# Wisol-Breakout.net
KiCad netlist of a schematic drawn in EAGLE
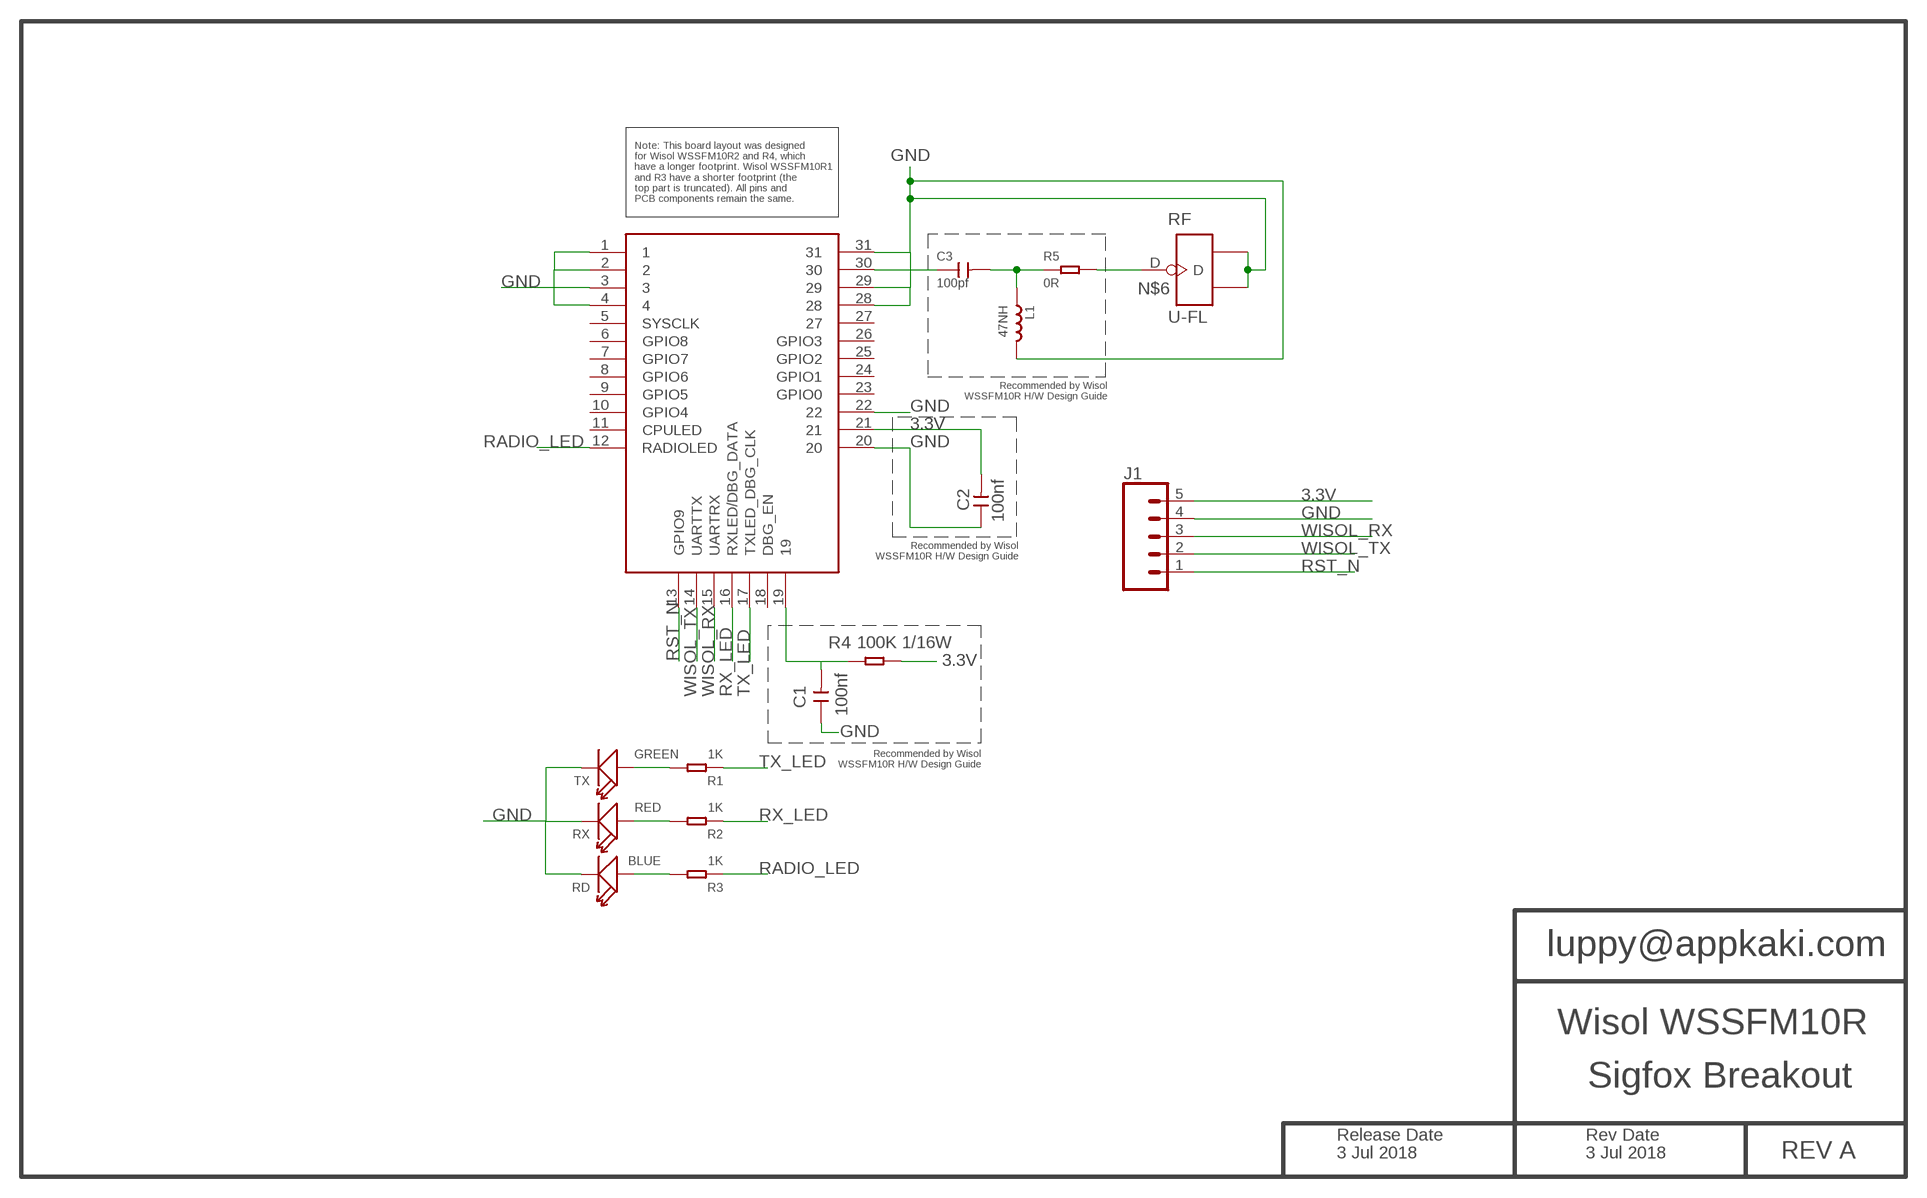
[diagram p0: schematic, sheet 1]

(export (version "E")
  (design (tool "Eeschema 10.0.6"))
  (components
    (comp (ref "C1")
      (value "100nf")
      (footprint "eagle-import:C0402")
      (fields (field (name "MPN") "CC0402KRX7R8BB104"))
      (libsource (lib "eagle-import") (part "CERAMIC-100NF-25V-10%-X7R(0402)"))
    )
    (comp (ref "C2")
      (value "100nf")
      (footprint "eagle-import:C0402")
      (fields (field (name "MPN") "CC0402KRX7R8BB104"))
      (libsource (lib "eagle-import") (part "CERAMIC-100NF-25V-10%-X7R(0402)"))
    )
    (comp (ref "C3")
      (value "100pf")
      (footprint "eagle-import:C0402")
      (fields (field (name "MPN") "CC0402JRNPO9BN101"))
      (libsource (lib "eagle-import") (part "CERAMIC-100PF-50V-5%-NPO(0402)"))
    )
    (comp (ref "J1")
      (value "CONN_05")
      (footprint "eagle-import:1X05")
      (libsource (lib "eagle-import") (part "CONN_05"))
    )
    (comp (ref "L1")
      (value "47NH")
      (footprint "eagle-import:L0402")
      (fields (field (name "MPN") "LQG15HS15NJ02") (field (name "MPN_1") "LQW15AN47NJ00D"))
      (libsource (lib "eagle-import") (part "SMD-INDUCTOR-15NH-5%-300MA(0402)"))
    )
    (comp (ref "R1")
      (value "1K")
      (footprint "eagle-import:R0402")
      (fields (field (name "MPN") "RC0402JR-071KL") (field (name "MPN_1") "RC0402FR-071KL"))
      (libsource (lib "eagle-import") (part "SMD-RES-1K-5%-1/16W(0402)"))
    )
    (comp (ref "R2")
      (value "1K")
      (footprint "eagle-import:R0402")
      (fields (field (name "MPN") "RC0402JR-071KL") (field (name "MPN_1") "RC0402FR-071KL"))
      (libsource (lib "eagle-import") (part "SMD-RES-1K-5%-1/16W(0402)"))
    )
    (comp (ref "R3")
      (value "1K")
      (footprint "eagle-import:R0402")
      (fields (field (name "MPN") "RC0402JR-071KL") (field (name "MPN_1") "RC0402FR-071KL"))
      (libsource (lib "eagle-import") (part "SMD-RES-1K-5%-1/16W(0402)"))
    )
    (comp (ref "R4")
      (value "100K 1/16W")
      (footprint "eagle-import:R0402")
      (fields (field (name "MPN") "RC0402JR-07100KL"))
      (libsource (lib "eagle-import") (part "SMD-RES-100K-5%-1/16W(0402)"))
    )
    (comp (ref "R5")
      (value "0R")
      (footprint "eagle-import:R0402")
      (fields (field (name "MPN") "RC0402JR-070RL"))
      (libsource (lib "eagle-import") (part "SMD-RES-0R-5%-1/16W(0402)"))
    )
    (comp (ref "RD")
      (value "BLUE")
      (footprint "eagle-import:LED-0603")
      (fields (field (name "MPN") "19-217-BHC-ZL1M2RY-3T"))
      (libsource (lib "eagle-import") (part "SMD-LED-CLEAR-BLUE(0603)"))
    )
    (comp (ref "RF")
      (value "U-FL")
      (footprint "eagle-import:U-FL3P-SMD-2.6X2.6X1.0MM")
      (libsource (lib "eagle-import") (part "ANTENNA-CONN-U-FL(3P)"))
    )
    (comp (ref "RX")
      (value "RED")
      (footprint "eagle-import:LED-0603")
      (fields (field (name "MPN") "19-217-R6C-AL1M2VY-3T"))
      (libsource (lib "eagle-import") (part "LED-SMD-RED-DIFFUSED(0603)"))
    )
    (comp (ref "TX")
      (value "GREEN")
      (footprint "eagle-import:LED-0603")
      (fields (field (name "MPN") "19-217-G7C-AN1P2-3T"))
      (libsource (lib "eagle-import") (part "SMD-LED-CLEAR-GREEN(0603)"))
    )
    (comp (ref "WSSFM10R")
      (value "WSSFM10RWSSFM10R2R4")
      (footprint "eagle-import:WSSFM10R")
      (libsource (lib "eagle-import") (part "WSSFM10RWSSFM10R2R4"))
    )
  )
  (nets
    (net (code "1") (name "/3.3V") (class "Default")
      (node (ref "C2") (pin "2") (pinfunction "2_2") (pintype "passive"))
      (node (ref "J1") (pin "5") (pinfunction "5_5") (pintype "passive"))
      (node (ref "R4") (pin "2") (pinfunction "2_2") (pintype "passive"))
      (node (ref "WSSFM10R") (pin "21") (pinfunction "21_21") (pintype "bidirectional"))
    )
    (net (code "2") (name "/GND") (class "Default")
      (node (ref "C1") (pin "1") (pinfunction "1_1") (pintype "passive"))
      (node (ref "C2") (pin "1") (pinfunction "1_1") (pintype "passive"))
      (node (ref "J1") (pin "4") (pinfunction "4_4") (pintype "passive"))
      (node (ref "L1") (pin "2") (pinfunction "2_2") (pintype "passive"))
      (node (ref "RD") (pin "-") (pinfunction "-_-") (pintype "passive"))
      (node (ref "RF") (pin "GND1") (pinfunction "GND1_GND1") (pintype "bidirectional"))
      (node (ref "RF") (pin "GND2") (pinfunction "GND2_GND2") (pintype "bidirectional"))
      (node (ref "RX") (pin "-") (pinfunction "-_-") (pintype "passive"))
      (node (ref "TX") (pin "-") (pinfunction "-_-") (pintype "passive"))
      (node (ref "WSSFM10R") (pin "1") (pinfunction "1_1") (pintype "bidirectional"))
      (node (ref "WSSFM10R") (pin "2") (pinfunction "2_2") (pintype "bidirectional"))
      (node (ref "WSSFM10R") (pin "20") (pinfunction "20_20") (pintype "bidirectional"))
      (node (ref "WSSFM10R") (pin "22") (pinfunction "22_22") (pintype "bidirectional"))
      (node (ref "WSSFM10R") (pin "28") (pinfunction "28_28") (pintype "bidirectional"))
      (node (ref "WSSFM10R") (pin "29") (pinfunction "29_29") (pintype "bidirectional"))
      (node (ref "WSSFM10R") (pin "3") (pinfunction "3_3") (pintype "bidirectional"))
      (node (ref "WSSFM10R") (pin "31") (pinfunction "31_31") (pintype "bidirectional"))
      (node (ref "WSSFM10R") (pin "4") (pinfunction "4_4") (pintype "bidirectional"))
    )
    (net (code "3") (name "/N$6") (class "Default")
      (node (ref "R5") (pin "2") (pinfunction "2_2") (pintype "passive"))
      (node (ref "RF") (pin "D") (pinfunction "D_D") (pintype "bidirectional"))
    )
    (net (code "4") (name "/RADIO_LED") (class "Default")
      (node (ref "R3") (pin "1") (pinfunction "1_1") (pintype "passive"))
      (node (ref "WSSFM10R") (pin "12") (pinfunction "RADIOLED_12") (pintype "bidirectional"))
    )
    (net (code "5") (name "/RST_N") (class "Default")
      (node (ref "J1") (pin "1") (pinfunction "1_1") (pintype "passive"))
      (node (ref "WSSFM10R") (pin "13") (pinfunction "GPIO9_13") (pintype "bidirectional"))
    )
    (net (code "6") (name "/RX_LED") (class "Default")
      (node (ref "R2") (pin "1") (pinfunction "1_1") (pintype "passive"))
      (node (ref "WSSFM10R") (pin "16") (pinfunction "RXLED/DBG_DATA_16") (pintype "bidirectional"))
    )
    (net (code "7") (name "/TX_LED") (class "Default")
      (node (ref "R1") (pin "1") (pinfunction "1_1") (pintype "passive"))
      (node (ref "WSSFM10R") (pin "17") (pinfunction "TXLED_DBG_CLK_17") (pintype "bidirectional"))
    )
    (net (code "8") (name "/WISOL_RX") (class "Default")
      (node (ref "J1") (pin "3") (pinfunction "3_3") (pintype "passive"))
      (node (ref "WSSFM10R") (pin "15") (pinfunction "UARTRX_15") (pintype "bidirectional"))
    )
    (net (code "9") (name "/WISOL_TX") (class "Default")
      (node (ref "J1") (pin "2") (pinfunction "2_2") (pintype "passive"))
      (node (ref "WSSFM10R") (pin "14") (pinfunction "UARTTX_14") (pintype "bidirectional"))
    )
    (net (code "10") (name "Net-(C1-Pad2)") (class "Default")
      (node (ref "C1") (pin "2") (pinfunction "2_2") (pintype "passive"))
      (node (ref "R4") (pin "1") (pinfunction "1_1") (pintype "passive"))
      (node (ref "WSSFM10R") (pin "19") (pinfunction "19_19") (pintype "bidirectional"))
    )
    (net (code "11") (name "Net-(C3-Pad1)") (class "Default")
      (node (ref "C3") (pin "1") (pinfunction "1_1") (pintype "passive"))
      (node (ref "WSSFM10R") (pin "30") (pinfunction "30_30") (pintype "bidirectional"))
    )
    (net (code "12") (name "Net-(C3-Pad2)") (class "Default")
      (node (ref "C3") (pin "2") (pinfunction "2_2") (pintype "passive"))
      (node (ref "L1") (pin "1") (pinfunction "1_1") (pintype "passive"))
      (node (ref "R5") (pin "1") (pinfunction "1_1") (pintype "passive"))
    )
    (net (code "13") (name "Net-(R1-Pad2)") (class "Default")
      (node (ref "R1") (pin "2") (pinfunction "2_2") (pintype "passive"))
      (node (ref "TX") (pin "+") (pinfunction "+_+") (pintype "passive"))
    )
    (net (code "14") (name "Net-(R2-Pad2)") (class "Default")
      (node (ref "R2") (pin "2") (pinfunction "2_2") (pintype "passive"))
      (node (ref "RX") (pin "+") (pinfunction "+_+") (pintype "passive"))
    )
    (net (code "15") (name "Net-(R3-Pad2)") (class "Default")
      (node (ref "R3") (pin "2") (pinfunction "2_2") (pintype "passive"))
      (node (ref "RD") (pin "+") (pinfunction "+_+") (pintype "passive"))
    )
    (net (code "16") (name "unconnected-(WSSFM10R-CPULED-Pad11)") (class "Default")
      (node (ref "WSSFM10R") (pin "11") (pinfunction "CPULED_11") (pintype "bidirectional"))
    )
    (net (code "17") (name "unconnected-(WSSFM10R-DBG_EN-Pad18)") (class "Default")
      (node (ref "WSSFM10R") (pin "18") (pinfunction "DBG_EN_18") (pintype "bidirectional"))
    )
    (net (code "18") (name "unconnected-(WSSFM10R-GPIO0-Pad23)") (class "Default")
      (node (ref "WSSFM10R") (pin "23") (pinfunction "GPIO0_23") (pintype "bidirectional"))
    )
    (net (code "19") (name "unconnected-(WSSFM10R-GPIO1-Pad24)") (class "Default")
      (node (ref "WSSFM10R") (pin "24") (pinfunction "GPIO1_24") (pintype "bidirectional"))
    )
    (net (code "20") (name "unconnected-(WSSFM10R-GPIO2-Pad25)") (class "Default")
      (node (ref "WSSFM10R") (pin "25") (pinfunction "GPIO2_25") (pintype "bidirectional"))
    )
    (net (code "21") (name "unconnected-(WSSFM10R-GPIO3-Pad26)") (class "Default")
      (node (ref "WSSFM10R") (pin "26") (pinfunction "GPIO3_26") (pintype "bidirectional"))
    )
    (net (code "22") (name "unconnected-(WSSFM10R-GPIO4-Pad10)") (class "Default")
      (node (ref "WSSFM10R") (pin "10") (pinfunction "GPIO4_10") (pintype "bidirectional"))
    )
    (net (code "23") (name "unconnected-(WSSFM10R-GPIO5-Pad9)") (class "Default")
      (node (ref "WSSFM10R") (pin "9") (pinfunction "GPIO5_9") (pintype "bidirectional"))
    )
    (net (code "24") (name "unconnected-(WSSFM10R-GPIO6-Pad8)") (class "Default")
      (node (ref "WSSFM10R") (pin "8") (pinfunction "GPIO6_8") (pintype "bidirectional"))
    )
    (net (code "25") (name "unconnected-(WSSFM10R-GPIO7-Pad7)") (class "Default")
      (node (ref "WSSFM10R") (pin "7") (pinfunction "GPIO7_7") (pintype "bidirectional"))
    )
    (net (code "26") (name "unconnected-(WSSFM10R-GPIO8-Pad6)") (class "Default")
      (node (ref "WSSFM10R") (pin "6") (pinfunction "GPIO8_6") (pintype "bidirectional"))
    )
    (net (code "27") (name "unconnected-(WSSFM10R-Pad27)") (class "Default")
      (node (ref "WSSFM10R") (pin "27") (pinfunction "27_27") (pintype "bidirectional"))
    )
    (net (code "28") (name "unconnected-(WSSFM10R-SYSCLK-Pad5)") (class "Default")
      (node (ref "WSSFM10R") (pin "5") (pinfunction "SYSCLK_5") (pintype "bidirectional"))
    )
  )
)
